# USB.net
KiCad netlist of a schematic drawn in Altium Designer
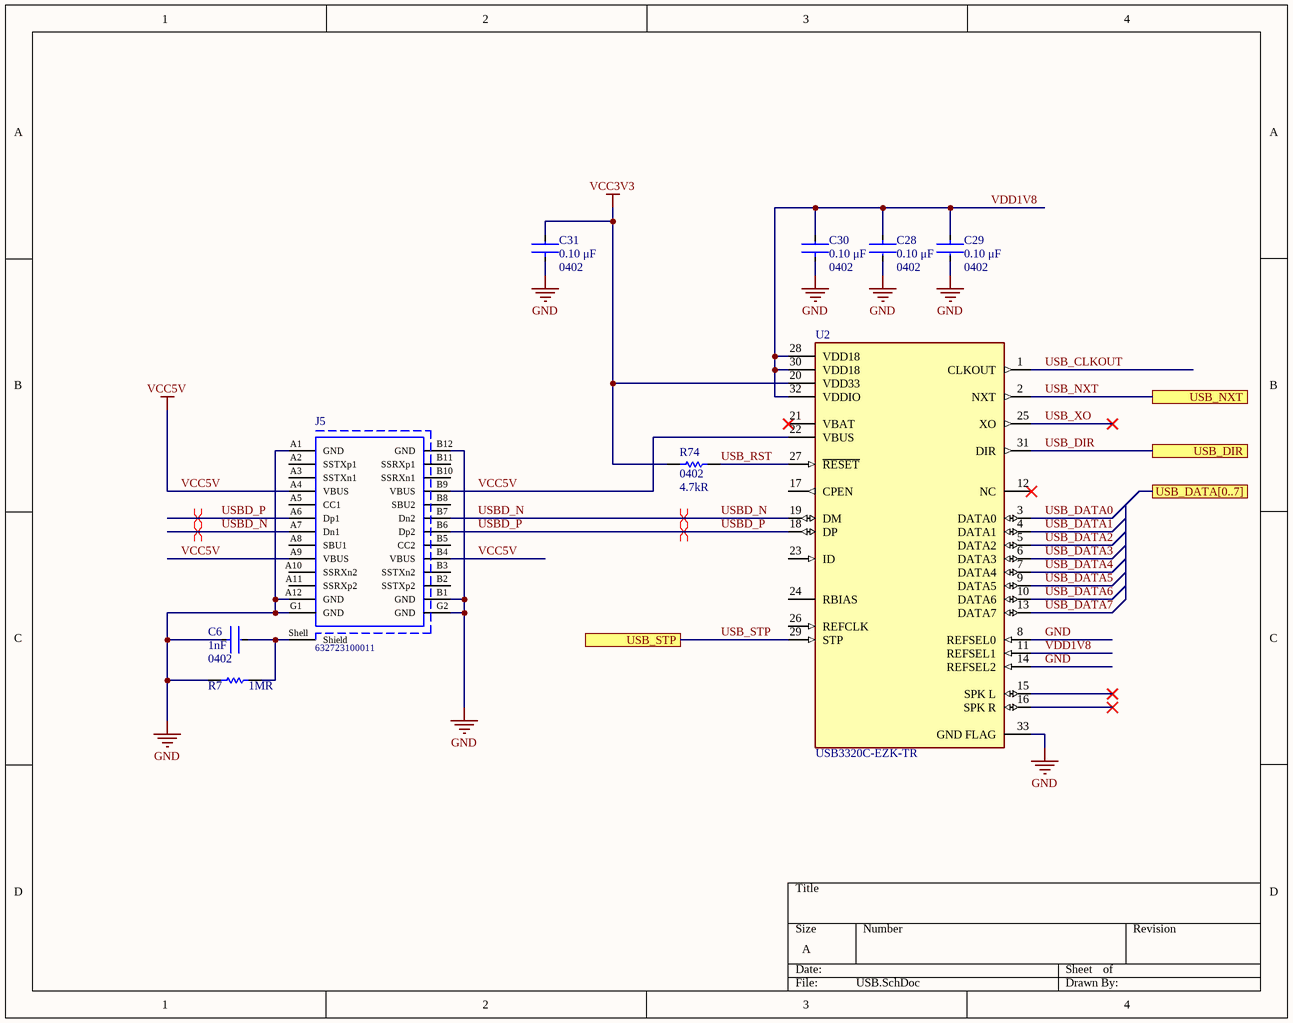
[diagram p0: USB.SchDoc]

(export (version "E")
  (design (tool "Eeschema 10.0.6"))
  (components
    (comp (ref "C6")
      (value "GRM1555C1H102JA01D")
      (footprint "FP-GRM155-0_05-IPC_B")
      (description "Chip Multilayer Ceramic Capacitors for General Purpose, 0402, 1000pF, C0G, 30ppm/°C, 5%, 50V")
      (fields
        (field (name "TOLERANCE") "5%")
        (field (name "VOLTAGE") "50V")
        (field (name "CASE/PACKAGE") "0402")
        (field (name "CAPACITANCE") "1nF")
      )
      (libsource (lib "Altium Content Vault") (part "02cd4be3c70576c341d710602a673aa"))
    )
    (comp (ref "C28")
      (value "0.10 μF")
      (footprint "FP-C0402-BB-MFG")
      (description "CAP CER 0.1UF 10V X5R 0402")
      (fields
        (field (name "MANUFACTURER") "Kemet")
        (field (name "TOLERANCE") "0.1")
        (field (name "CASE/PACKAGE") "0402")
      )
      (libsource (lib "Altium Content Vault") (part "b4654b650e69147ec39a6b967a45e02"))
    )
    (comp (ref "C29")
      (value "0.10 μF")
      (footprint "FP-C0402-BB-MFG")
      (description "CAP CER 0.1UF 10V X5R 0402")
      (fields
        (field (name "MANUFACTURER") "Kemet")
        (field (name "TOLERANCE") "0.1")
        (field (name "CASE/PACKAGE") "0402")
      )
      (libsource (lib "Altium Content Vault") (part "b4654b650e69147ec39a6b967a45e02"))
    )
    (comp (ref "C30")
      (value "0.10 μF")
      (footprint "FP-C0402-BB-MFG")
      (description "CAP CER 0.1UF 10V X5R 0402")
      (fields
        (field (name "MANUFACTURER") "Kemet")
        (field (name "TOLERANCE") "0.1")
        (field (name "CASE/PACKAGE") "0402")
      )
      (libsource (lib "Altium Content Vault") (part "b4654b650e69147ec39a6b967a45e02"))
    )
    (comp (ref "C31")
      (value "0.10 μF")
      (footprint "FP-C0402-BB-MFG")
      (description "CAP CER 0.1UF 10V X5R 0402")
      (fields
        (field (name "MANUFACTURER") "Kemet")
        (field (name "TOLERANCE") "0.1")
        (field (name "CASE/PACKAGE") "0402")
      )
      (libsource (lib "Altium Content Vault") (part "b4654b650e69147ec39a6b967a45e02"))
    )
    (comp (ref "J5")
      (value "632723100011")
      (footprint "632723100011")
      (description "USB 3.1 Type C Receptacle WR-COM, Horizontal, SMT / THT")
      (fields (field (name "MANUFACTURER") "Wurth Elektronik") (field (name "PUBLISHER") "WurthElektronik"))
      (libsource (lib "Altium Content Vault") (part "WE-632723X00011"))
    )
    (comp (ref "R7")
      (value "1MR")
      (footprint "RESC1005X40X25LL05T05")
      (description "Chip Resistor, 1 MOhm, +/- 1%, 100 mW, -55 to 155 degC, 0402 (1005 Metric), RoHS, Tape and Reel")
      (fields (field (name "PARTNUMBER") "ERJ-2RKF1004X") (field (name "TOLERANCE") "1%"))
      (libsource (lib "Altium Content Vault") (part "RES-2"))
    )
    (comp (ref "R74")
      (value "4.7kR")
      (footprint "RESC1005X40X25LL05T05")
      (description "Chip Resistor, 4.7 KOhm, +/- 1%, 0.1 W, -55 to 155 degC, 0402 (1005 Metric), RoHS, Tape and Reel")
      (fields
        (field (name "PACKAGEREFERENCE") "0402")
        (field (name "TOLERANCE") "1%")
        (field (name "PARTNUMBER") "ERJ-2RKF4701X")
      )
      (libsource (lib "Altium Content Vault") (part "RES-2"))
    )
    (comp (ref "U2")
      (value "USB3320C-EZK-TR")
      (footprint "FP-32QFN-3304-5X5B-MFG")
      (description "IC TRANSCEIVER HALF 1/1 32QFN")
      (fields
        (field (name "MANUFACTURER") "Microchip")
        (field (name "OCTOPART") "https://octopart.com/usb3320c-ezk-tr-microchip-24995468")
      )
      (libsource (lib "Altium Content Vault") (part "d497a40fedd2315480c30a8e5861190"))
    )
  )
  (nets
    (net (code "1") (name "/USBD_N") (class "Default")
      (node (ref "J5") (pin "A7") (pinfunction "Dn1_A7") (pintype "passive"))
      (node (ref "J5") (pin "B7") (pinfunction "Dn2_B7") (pintype "passive"))
      (node (ref "U2") (pin "19") (pinfunction "DM_19") (pintype "bidirectional"))
    )
    (net (code "2") (name "/USBD_P") (class "Default")
      (node (ref "J5") (pin "A6") (pinfunction "Dp1_A6") (pintype "passive"))
      (node (ref "J5") (pin "B6") (pinfunction "Dp2_B6") (pintype "passive"))
      (node (ref "U2") (pin "18") (pinfunction "DP_18") (pintype "bidirectional"))
    )
    (net (code "3") (name "/USB_CLKOUT") (class "Default")
      (node (ref "U2") (pin "1") (pinfunction "CLKOUT_1") (pintype "output"))
    )
    (net (code "4") (name "/USB_DATA0") (class "Default")
      (node (ref "U2") (pin "3") (pinfunction "DATA0_3") (pintype "bidirectional"))
    )
    (net (code "5") (name "/USB_DATA1") (class "Default")
      (node (ref "U2") (pin "4") (pinfunction "DATA1_4") (pintype "bidirectional"))
    )
    (net (code "6") (name "/USB_DATA2") (class "Default")
      (node (ref "U2") (pin "5") (pinfunction "DATA2_5") (pintype "bidirectional"))
    )
    (net (code "7") (name "/USB_DATA3") (class "Default")
      (node (ref "U2") (pin "6") (pinfunction "DATA3_6") (pintype "bidirectional"))
    )
    (net (code "8") (name "/USB_DATA4") (class "Default")
      (node (ref "U2") (pin "7") (pinfunction "DATA4_7") (pintype "bidirectional"))
    )
    (net (code "9") (name "/USB_DATA5") (class "Default")
      (node (ref "U2") (pin "9") (pinfunction "DATA5_9") (pintype "bidirectional"))
    )
    (net (code "10") (name "/USB_DATA6") (class "Default")
      (node (ref "U2") (pin "10") (pinfunction "DATA6_10") (pintype "bidirectional"))
    )
    (net (code "11") (name "/USB_DATA7") (class "Default")
      (node (ref "U2") (pin "13") (pinfunction "DATA7_13") (pintype "bidirectional"))
    )
    (net (code "13") (name "/USB_DIR") (class "Default")
      (node (ref "U2") (pin "31") (pinfunction "DIR_31") (pintype "output"))
    )
    (net (code "14") (name "/USB_NXT") (class "Default")
      (node (ref "U2") (pin "2") (pinfunction "NXT_2") (pintype "output"))
    )
    (net (code "15") (name "/USB_RST") (class "Default")
      (node (ref "R74") (pin "1") (pinfunction "1_1") (pintype "passive"))
      (node (ref "U2") (pin "27") (pinfunction "~{RESET}_27") (pintype "input"))
    )
    (net (code "16") (name "/USB_STP") (class "Default")
      (node (ref "U2") (pin "29") (pinfunction "STP_29") (pintype "input"))
    )
    (net (code "17") (name "/USB_XO") (class "Default")
      (node (ref "U2") (pin "25") (pinfunction "XO_25") (pintype "output+no_connect"))
    )
    (net (code "18") (name "/VDD1V8") (class "Default")
      (node (ref "C28") (pin "1") (pinfunction "1_1") (pintype "passive"))
      (node (ref "C29") (pin "1") (pinfunction "1_1") (pintype "passive"))
      (node (ref "C30") (pin "2") (pinfunction "2_2") (pintype "passive"))
      (node (ref "U2") (pin "11") (pinfunction "REFSEL1_11") (pintype "input"))
      (node (ref "U2") (pin "28") (pinfunction "VDD18_28") (pintype "power_in"))
      (node (ref "U2") (pin "30") (pinfunction "VDD18_30") (pintype "power_in"))
      (node (ref "U2") (pin "32") (pinfunction "VDDIO_32") (pintype "power_in"))
    )
    (net (code "19") (name "GND") (class "Default")
      (node (ref "C28") (pin "2") (pinfunction "2_2") (pintype "passive"))
      (node (ref "C29") (pin "2") (pinfunction "2_2") (pintype "passive"))
      (node (ref "C30") (pin "1") (pinfunction "1_1") (pintype "passive"))
      (node (ref "C31") (pin "1") (pinfunction "1_1") (pintype "passive"))
      (node (ref "C6") (pin "1") (pinfunction "1_1") (pintype "passive"))
      (node (ref "J5") (pin "A1") (pinfunction "GND_A1") (pintype "passive"))
      (node (ref "J5") (pin "A12") (pinfunction "GND_A12") (pintype "passive"))
      (node (ref "J5") (pin "B1") (pinfunction "GND_B1") (pintype "passive"))
      (node (ref "J5") (pin "B12") (pinfunction "GND_B12") (pintype "passive"))
      (node (ref "J5") (pin "G1") (pinfunction "GND_G1") (pintype "passive"))
      (node (ref "J5") (pin "G2") (pinfunction "GND_G2") (pintype "passive"))
      (node (ref "R7") (pin "1") (pinfunction "1_1") (pintype "passive"))
      (node (ref "U2") (pin "14") (pinfunction "REFSEL2_14") (pintype "input"))
      (node (ref "U2") (pin "33") (pinfunction "GND_FLAG_33") (pintype "power_in"))
      (node (ref "U2") (pin "8") (pinfunction "REFSEL0_8") (pintype "input"))
    )
    (net (code "20") (name "Net-(J5-Shield)") (class "Default")
      (node (ref "C6") (pin "2") (pinfunction "2_2") (pintype "passive"))
      (node (ref "J5") (pin "Shell") (pinfunction "Shield_Shell") (pintype "passive"))
      (node (ref "R7") (pin "2") (pinfunction "2_2") (pintype "passive"))
    )
    (net (code "21") (name "VCC3V3") (class "Default")
      (node (ref "C31") (pin "2") (pinfunction "2_2") (pintype "passive"))
      (node (ref "R74") (pin "2") (pinfunction "2_2") (pintype "passive"))
      (node (ref "U2") (pin "20") (pinfunction "VDD33_20") (pintype "power_in"))
    )
    (net (code "22") (name "VCC5V") (class "Default")
      (node (ref "J5") (pin "A4") (pinfunction "VBUS_A4") (pintype "passive"))
      (node (ref "J5") (pin "A9") (pinfunction "VBUS_A9") (pintype "passive"))
      (node (ref "J5") (pin "B4") (pinfunction "VBUS_B4") (pintype "passive"))
      (node (ref "J5") (pin "B9") (pinfunction "VBUS_B9") (pintype "passive"))
      (node (ref "U2") (pin "22") (pinfunction "VBUS_22") (pintype "power_in"))
    )
    (net (code "23") (name "unconnected-(J5-CC1-PadA5)") (class "Default")
      (node (ref "J5") (pin "A5") (pinfunction "CC1_A5") (pintype "passive"))
    )
    (net (code "24") (name "unconnected-(J5-CC2-PadB5)") (class "Default")
      (node (ref "J5") (pin "B5") (pinfunction "CC2_B5") (pintype "passive"))
    )
    (net (code "25") (name "unconnected-(J5-SBU1-PadA8)") (class "Default")
      (node (ref "J5") (pin "A8") (pinfunction "SBU1_A8") (pintype "passive"))
    )
    (net (code "26") (name "unconnected-(J5-SBU2-PadB8)") (class "Default")
      (node (ref "J5") (pin "B8") (pinfunction "SBU2_B8") (pintype "passive"))
    )
    (net (code "27") (name "unconnected-(J5-SSRXn1-PadB10)") (class "Default")
      (node (ref "J5") (pin "B10") (pinfunction "SSRXn1_B10") (pintype "passive"))
    )
    (net (code "28") (name "unconnected-(J5-SSRXn2-PadA10)") (class "Default")
      (node (ref "J5") (pin "A10") (pinfunction "SSRXn2_A10") (pintype "passive"))
    )
    (net (code "29") (name "unconnected-(J5-SSRXp1-PadB11)") (class "Default")
      (node (ref "J5") (pin "B11") (pinfunction "SSRXp1_B11") (pintype "passive"))
    )
    (net (code "30") (name "unconnected-(J5-SSRXp2-PadA11)") (class "Default")
      (node (ref "J5") (pin "A11") (pinfunction "SSRXp2_A11") (pintype "passive"))
    )
    (net (code "31") (name "unconnected-(J5-SSTXn1-PadA3)") (class "Default")
      (node (ref "J5") (pin "A3") (pinfunction "SSTXn1_A3") (pintype "passive"))
    )
    (net (code "32") (name "unconnected-(J5-SSTXn2-PadB3)") (class "Default")
      (node (ref "J5") (pin "B3") (pinfunction "SSTXn2_B3") (pintype "passive"))
    )
    (net (code "33") (name "unconnected-(J5-SSTXp1-PadA2)") (class "Default")
      (node (ref "J5") (pin "A2") (pinfunction "SSTXp1_A2") (pintype "passive"))
    )
    (net (code "34") (name "unconnected-(J5-SSTXp2-PadB2)") (class "Default")
      (node (ref "J5") (pin "B2") (pinfunction "SSTXp2_B2") (pintype "passive"))
    )
    (net (code "35") (name "unconnected-(U2-CPEN-Pad17)") (class "Default")
      (node (ref "U2") (pin "17") (pinfunction "CPEN_17") (pintype "output"))
    )
    (net (code "36") (name "unconnected-(U2-ID-Pad23)") (class "Default")
      (node (ref "U2") (pin "23") (pinfunction "ID_23") (pintype "input"))
    )
    (net (code "37") (name "unconnected-(U2-NC-Pad12)") (class "Default")
      (node (ref "U2") (pin "12") (pinfunction "NC_12") (pintype "passive+no_connect"))
    )
    (net (code "38") (name "unconnected-(U2-RBIAS-Pad24)") (class "Default")
      (node (ref "U2") (pin "24") (pinfunction "RBIAS_24") (pintype "power_in"))
    )
    (net (code "39") (name "unconnected-(U2-REFCLK-Pad26)") (class "Default")
      (node (ref "U2") (pin "26") (pinfunction "REFCLK_26") (pintype "input"))
    )
    (net (code "40") (name "unconnected-(U2-SPK_L-Pad15)") (class "Default")
      (node (ref "U2") (pin "15") (pinfunction "SPK_L_15") (pintype "bidirectional+no_connect"))
    )
    (net (code "41") (name "unconnected-(U2-SPK_R-Pad16)") (class "Default")
      (node (ref "U2") (pin "16") (pinfunction "SPK_R_16") (pintype "bidirectional+no_connect"))
    )
    (net (code "42") (name "unconnected-(U2-VBAT-Pad21)") (class "Default")
      (node (ref "U2") (pin "21") (pinfunction "VBAT_21") (pintype "power_in+no_connect"))
    )
  )
)
